# Sheet2.net
KiCad netlist of a schematic drawn in Altium Designer
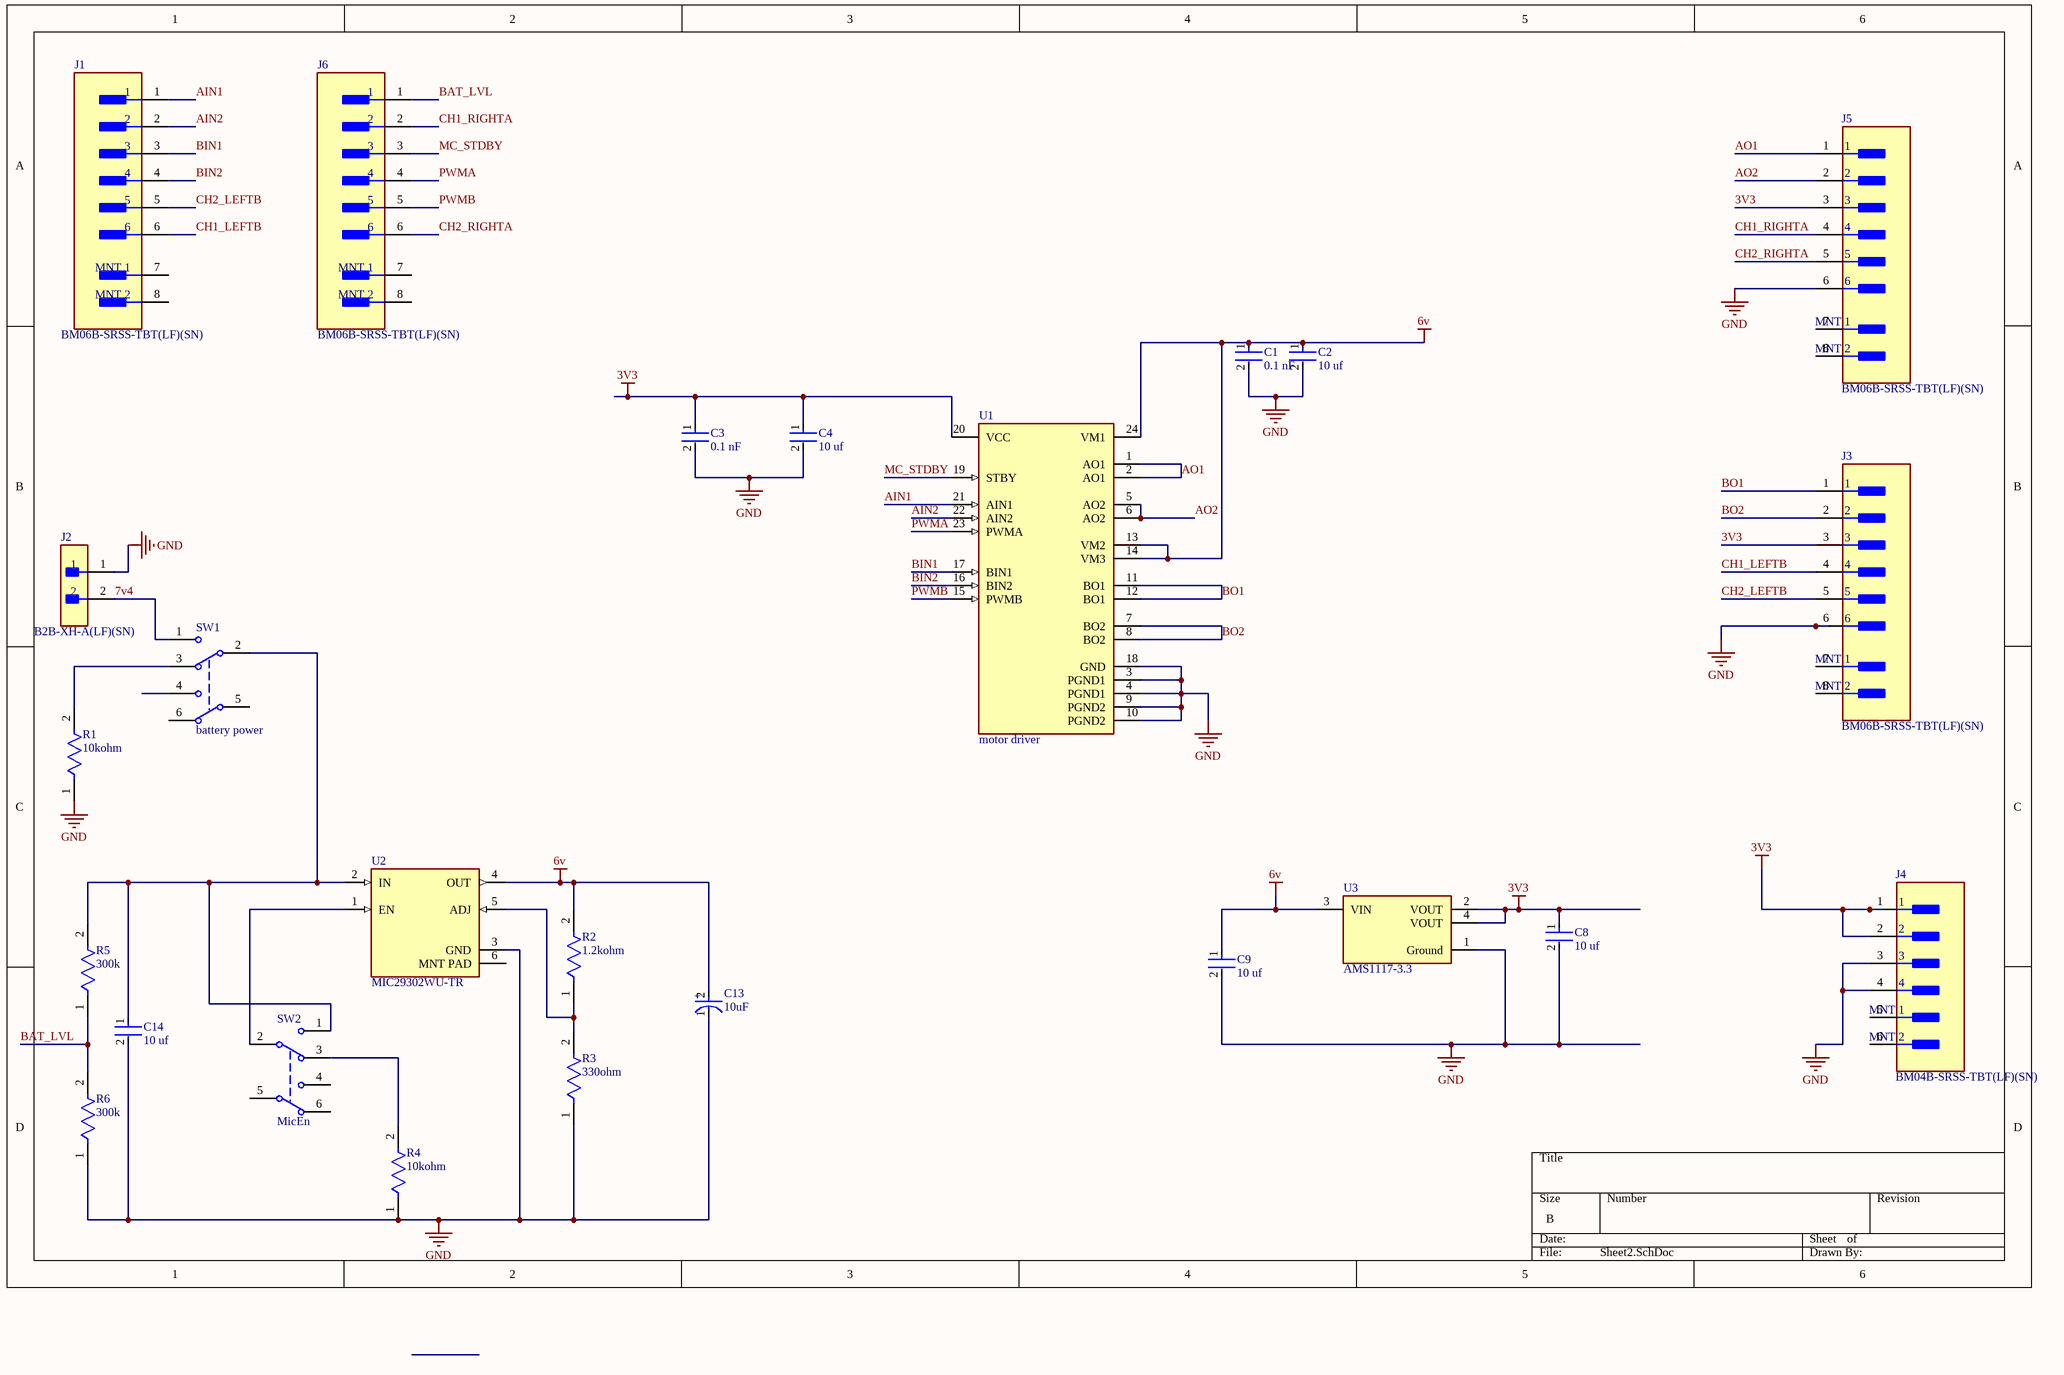
[diagram p0: Sheet2.SchDoc]

(export (version "E")
  (design (tool "Eeschema 10.0.6"))
  (components
    (comp (ref "C1")
      (value "0.1 nF")
      (footprint "FP-CC0805-0_85-MFG")
      (description "CAP CER 0.1UF 50V X7R 0805")
      (fields (field (name "TOLERANCE") "0.1") (field (name "MANUFACTURER PART NUMBER") "CC0805KRX7R9BB104"))
      (libsource (lib "Altium Content Vault") (part "11868f565c42a9108669ba33697ecf6"))
    )
    (comp (ref "C2")
      (value "10 uf")
      (footprint "FP-CC0805-0_2-1_45-IPC_A")
      (description "CAP CER 10UF 10V X5R 0805")
      (fields (field (name "VOLTAGE") "10V") (field (name "TOLERANCE") "10%"))
      (libsource (lib "Altium Content Vault") (part "e9c51b7dd13d4faca003ae77663ab08"))
    )
    (comp (ref "C3")
      (value "0.1 nF")
      (footprint "FP-CC0805-0_85-MFG")
      (description "CAP CER 0.1UF 50V X7R 0805")
      (fields (field (name "TOLERANCE") "0.1") (field (name "MANUFACTURER PART NUMBER") "CC0805KRX7R9BB104"))
      (libsource (lib "Altium Content Vault") (part "11868f565c42a9108669ba33697ecf6"))
    )
    (comp (ref "C4")
      (value "10 uf")
      (footprint "FP-CC0805-0_2-1_45-IPC_A")
      (description "CAP CER 10UF 10V X5R 0805")
      (fields (field (name "VOLTAGE") "10V") (field (name "TOLERANCE") "10%"))
      (libsource (lib "Altium Content Vault") (part "e9c51b7dd13d4faca003ae77663ab08"))
    )
    (comp (ref "C8")
      (value "10 uf")
      (footprint "FP-CC0805-0_2-1_45-IPC_A")
      (description "CAP CER 10UF 10V X5R 0805")
      (fields (field (name "VOLTAGE") "10V") (field (name "TOLERANCE") "10%"))
      (libsource (lib "Altium Content Vault") (part "e9c51b7dd13d4faca003ae77663ab08"))
    )
    (comp (ref "C9")
      (value "10 uf")
      (footprint "FP-CC0805-0_2-1_45-IPC_A")
      (description "CAP CER 10UF 10V X5R 0805")
      (fields (field (name "VOLTAGE") "10V") (field (name "TOLERANCE") "10%"))
      (libsource (lib "Altium Content Vault") (part "e9c51b7dd13d4faca003ae77663ab08"))
    )
    (comp (ref "C13")
      (value "10uF")
      (footprint "FP-T491A105K016AT-MFG")
      (description "CAP TANT 1UF 10% 16V 1206")
      (fields (field (name "TOLERANCE") "20%") (field (name "VOLTAGE") "16V"))
      (libsource (lib "Altium Content Vault") (part "203bc49f2ac43e59fd269a8c329ed05"))
    )
    (comp (ref "C14")
      (value "10 uf")
      (footprint "FP-CC0805-0_2-1_45-IPC_A")
      (description "CAP CER 10UF 10V X5R 0805")
      (fields (field (name "VOLTAGE") "10V") (field (name "TOLERANCE") "10%"))
      (libsource (lib "Altium Content Vault") (part "e9c51b7dd13d4faca003ae77663ab08"))
    )
    (comp (ref "J1")
      (value "BM06B-SRSS-TBT(LF)(SN)")
      (footprint "FP-BM06B-SRSS-TBT_LF_SN-MFG")
      (description "CONN HEADER SMD 6POS 1MM")
      (libsource (lib "") (part "ed24c53d9ba001d1a2a686240a95171_1"))
    )
    (comp (ref "J2")
      (value "B2B-XH-A(LF)(SN)")
      (footprint "FP-B2B-XH-A_LF_SN-MFG")
      (description "CONN HEADER VERT 2POS 2.5MM")
      (libsource (lib "Altium Content Vault") (part "3bc925449376181038e59eaffc5286c"))
    )
    (comp (ref "J3")
      (value "BM06B-SRSS-TBT(LF)(SN)")
      (footprint "FP-BM06B-SRSS-TBT_LF_SN-MFG")
      (description "CONN HEADER SMD 6POS 1MM")
      (libsource (lib "Altium Content Vault") (part "ed24c53d9ba001d1a2a686240a95171"))
    )
    (comp (ref "J4")
      (value "BM04B-SRSS-TBT(LF)(SN)")
      (footprint "FP-BM04B-SRSS-TBT_LF_SN-MFG")
      (description "CONN HEADER SMD 4POS 1MM")
      (libsource (lib "Altium Content Vault") (part "8e3688c4b118bffc0dd9b7401e414ba"))
    )
    (comp (ref "J5")
      (value "BM06B-SRSS-TBT(LF)(SN)")
      (footprint "FP-BM06B-SRSS-TBT_LF_SN-MFG")
      (description "CONN HEADER SMD 6POS 1MM")
      (libsource (lib "Altium Content Vault") (part "ed24c53d9ba001d1a2a686240a95171"))
    )
    (comp (ref "J6")
      (value "BM06B-SRSS-TBT(LF)(SN)")
      (footprint "FP-BM06B-SRSS-TBT_LF_SN-MFG")
      (description "CONN HEADER SMD 6POS 1MM")
      (libsource (lib "") (part "ed24c53d9ba001d1a2a686240a95171_1"))
    )
    (comp (ref "R1")
      (value "10kohm")
      (footprint "FP-CR0805-IPC_B")
      (description "Thick Film Chip Resistors 0805 10kΩ 0.125W 5% 200ppm/°C")
      (fields (field (name "TOLERANCE") "5%"))
      (libsource (lib "Altium Content Vault") (part "1029c3af85768c4190bb7ad29bc67b5"))
    )
    (comp (ref "R2")
      (value "1.2kohm")
      (footprint "FP-CR0805-IPC_B")
      (description "Thick Film Chip Resistors 0805 1kΩ 0.125W 1% 100ppm/°C")
      (fields (field (name "TOLERANCE") "1%"))
      (libsource (lib "Altium Content Vault") (part "1029c3af85768c4190bb7ad29bc67b5"))
    )
    (comp (ref "R3")
      (value "330ohm")
      (footprint "FP-CR0805-IPC_B")
      (description "Thick Film Chip Resistors 0805 330Ω 0.125W 1% 100ppm/°C")
      (fields (field (name "TOLERANCE") "1%"))
      (libsource (lib "Altium Content Vault") (part "1029c3af85768c4190bb7ad29bc67b5"))
    )
    (comp (ref "R4")
      (value "10kohm")
      (footprint "FP-CR0805-IPC_B")
      (description "Thick Film Chip Resistors 0805 10kΩ 0.125W 5% 200ppm/°C")
      (fields (field (name "TOLERANCE") "5%"))
      (libsource (lib "Altium Content Vault") (part "1029c3af85768c4190bb7ad29bc67b5"))
    )
    (comp (ref "R5")
      (value "300k")
      (footprint "FP-CR0805-IPC_B")
      (description "Thick Film Chip Resistors 0805 10kΩ 0.125W 5% 200ppm/°C")
      (fields (field (name "TOLERANCE") "5%"))
      (libsource (lib "Altium Content Vault") (part "1029c3af85768c4190bb7ad29bc67b5"))
    )
    (comp (ref "R6")
      (value "300k")
      (footprint "FP-CR0805-IPC_B")
      (description "Thick Film Chip Resistors 0805 10kΩ 0.125W 5% 200ppm/°C")
      (fields (field (name "TOLERANCE") "5%"))
      (libsource (lib "Altium Content Vault") (part "1029c3af85768c4190bb7ad29bc67b5"))
    )
    (comp (ref "SW1")
      (value "battery power")
      (footprint "452404020202")
      (description "452404020202 Slide Switch, Dpdt, 0.3A, 6Vdc, Tht Rohs Compliant: Yes")
      (libsource (lib "Altium Content Vault") (part "DPDT"))
    )
    (comp (ref "SW2")
      (value "MicEn")
      (footprint "452404020202")
      (description "452404020202 Slide Switch, Dpdt, 0.3A, 6Vdc, Tht Rohs Compliant: Yes")
      (libsource (lib "Altium Content Vault") (part "DPDT"))
    )
    (comp (ref "U1")
      (value "motor driver")
      (footprint "FP-SSOP24-P-300-0_65A-IPC_A")
      (description "IC MOTOR DRIVER 2.7V-5.5V 24SSOP")
      (libsource (lib "Altium Content Vault") (part "0e8a2fe7f3780dc9c50f4d41012bdec"))
    )
    (comp (ref "U2")
      (value "MIC29302WU-TR")
      (footprint "FP-C04-012-MFG")
      (description "IC REG LINEAR POS ADJ 3A TO263-5")
      (fields
        (field (name "MANUFACTURER") "Microchip")
        (field (name "OCTOPART") "https://octopart.com/mic29302wu-tr-microchip-66801318")
      )
      (libsource (lib "Altium Content Vault") (part "0db40f55fda0e91d0d14528974a446d"))
    )
    (comp (ref "U3")
      (value "AMS1117-3.3")
      (footprint "FP-AMS1117-IPC_C")
      (description "LDO Voltage Regulators 1A, 3.3V")
      (fields
        (field (name "OCTOPART") "https://octopart.com/ams1117-3.3-advanced+monolithic+systems-25899300")
        (field (name "MANUFACTURER") "Advanced Monolithic Systems")
      )
      (libsource (lib "Altium Content Vault") (part "8bdbb5f8e77002000e30dd2845d0354"))
    )
  )
  (nets
    (net (code "1") (name "/7v4") (class "Default")
      (node (ref "J2") (pin "2") (pinfunction "2_2") (pintype "passive"))
      (node (ref "SW1") (pin "1") (pinfunction "1_1") (pintype "passive"))
    )
    (net (code "2") (name "/AIN1") (class "Default")
      (node (ref "J1") (pin "1") (pinfunction "1_1") (pintype "passive"))
      (node (ref "U1") (pin "21") (pinfunction "AIN1_21") (pintype "input"))
    )
    (net (code "3") (name "/AIN2") (class "Default")
      (node (ref "J1") (pin "2") (pinfunction "2_2") (pintype "passive"))
      (node (ref "U1") (pin "22") (pinfunction "AIN2_22") (pintype "input"))
    )
    (net (code "4") (name "/AO1") (class "Default")
      (node (ref "J5") (pin "1") (pinfunction "1_1") (pintype "passive"))
      (node (ref "U1") (pin "1") (pinfunction "AO1_1") (pintype "passive"))
      (node (ref "U1") (pin "2") (pinfunction "AO1_2") (pintype "passive"))
    )
    (net (code "5") (name "/AO2") (class "Default")
      (node (ref "J5") (pin "2") (pinfunction "2_2") (pintype "passive"))
      (node (ref "U1") (pin "5") (pinfunction "AO2_5") (pintype "passive"))
      (node (ref "U1") (pin "6") (pinfunction "AO2_6") (pintype "passive"))
    )
    (net (code "6") (name "/BAT_LVL") (class "Default")
      (node (ref "J6") (pin "1") (pinfunction "1_1") (pintype "passive"))
      (node (ref "R5") (pin "1") (pinfunction "1_1") (pintype "passive"))
      (node (ref "R6") (pin "2") (pinfunction "2_2") (pintype "passive"))
    )
    (net (code "7") (name "/BIN1") (class "Default")
      (node (ref "J1") (pin "3") (pinfunction "3_3") (pintype "passive"))
      (node (ref "U1") (pin "17") (pinfunction "BIN1_17") (pintype "input"))
    )
    (net (code "8") (name "/BIN2") (class "Default")
      (node (ref "J1") (pin "4") (pinfunction "4_4") (pintype "passive"))
      (node (ref "U1") (pin "16") (pinfunction "BIN2_16") (pintype "input"))
    )
    (net (code "9") (name "/BO1") (class "Default")
      (node (ref "J3") (pin "1") (pinfunction "1_1") (pintype "passive"))
      (node (ref "U1") (pin "11") (pinfunction "BO1_11") (pintype "passive"))
      (node (ref "U1") (pin "12") (pinfunction "BO1_12") (pintype "passive"))
    )
    (net (code "10") (name "/BO2") (class "Default")
      (node (ref "J3") (pin "2") (pinfunction "2_2") (pintype "passive"))
      (node (ref "U1") (pin "7") (pinfunction "BO2_7") (pintype "passive"))
      (node (ref "U1") (pin "8") (pinfunction "BO2_8") (pintype "passive"))
    )
    (net (code "11") (name "/CH1_LEFTB") (class "Default")
      (node (ref "J1") (pin "6") (pinfunction "6_6") (pintype "passive"))
      (node (ref "J3") (pin "4") (pinfunction "4_4") (pintype "passive"))
    )
    (net (code "12") (name "/CH1_RIGHTA") (class "Default")
      (node (ref "J5") (pin "4") (pinfunction "4_4") (pintype "passive"))
      (node (ref "J6") (pin "2") (pinfunction "2_2") (pintype "passive"))
    )
    (net (code "13") (name "/CH2_LEFTB") (class "Default")
      (node (ref "J1") (pin "5") (pinfunction "5_5") (pintype "passive"))
      (node (ref "J3") (pin "5") (pinfunction "5_5") (pintype "passive"))
    )
    (net (code "14") (name "/CH2_RIGHTA") (class "Default")
      (node (ref "J5") (pin "5") (pinfunction "5_5") (pintype "passive"))
      (node (ref "J6") (pin "6") (pinfunction "6_6") (pintype "passive"))
    )
    (net (code "15") (name "/MC_STDBY") (class "Default")
      (node (ref "J6") (pin "3") (pinfunction "3_3") (pintype "passive"))
      (node (ref "U1") (pin "19") (pinfunction "STBY_19") (pintype "input"))
    )
    (net (code "16") (name "/PWMA") (class "Default")
      (node (ref "J6") (pin "4") (pinfunction "4_4") (pintype "passive"))
      (node (ref "U1") (pin "23") (pinfunction "PWMA_23") (pintype "input"))
    )
    (net (code "17") (name "/PWMB") (class "Default")
      (node (ref "J6") (pin "5") (pinfunction "5_5") (pintype "passive"))
      (node (ref "U1") (pin "15") (pinfunction "PWMB_15") (pintype "input"))
    )
    (net (code "18") (name "3V3") (class "Default")
      (node (ref "C3") (pin "1") (pinfunction "1_1") (pintype "passive"))
      (node (ref "C4") (pin "1") (pinfunction "1_1") (pintype "passive"))
      (node (ref "C8") (pin "1") (pinfunction "1_1") (pintype "passive"))
      (node (ref "J3") (pin "3") (pinfunction "3_3") (pintype "passive"))
      (node (ref "J4") (pin "1") (pinfunction "1_1") (pintype "passive"))
      (node (ref "J4") (pin "2") (pinfunction "2_2") (pintype "passive"))
      (node (ref "J5") (pin "3") (pinfunction "3_3") (pintype "passive"))
      (node (ref "U1") (pin "20") (pinfunction "VCC_20") (pintype "power_in"))
      (node (ref "U3") (pin "2") (pinfunction "VOUT_2") (pintype "passive"))
      (node (ref "U3") (pin "4") (pinfunction "VOUT_4") (pintype "passive"))
    )
    (net (code "19") (name "6v") (class "Default")
      (node (ref "C1") (pin "1") (pinfunction "1_1") (pintype "passive"))
      (node (ref "C13") (pin "2") (pinfunction "A_2") (pintype "passive"))
      (node (ref "C2") (pin "1") (pinfunction "1_1") (pintype "passive"))
      (node (ref "C9") (pin "1") (pinfunction "1_1") (pintype "passive"))
      (node (ref "R2") (pin "2") (pinfunction "2_2") (pintype "passive"))
      (node (ref "U1") (pin "13") (pinfunction "VM2_13") (pintype "passive"))
      (node (ref "U1") (pin "14") (pinfunction "VM3_14") (pintype "passive"))
      (node (ref "U1") (pin "24") (pinfunction "VM1_24") (pintype "passive"))
      (node (ref "U2") (pin "4") (pinfunction "OUT_4") (pintype "output"))
      (node (ref "U3") (pin "3") (pinfunction "VIN_3") (pintype "passive"))
    )
    (net (code "20") (name "GND") (class "Default")
      (node (ref "C1") (pin "2") (pinfunction "2_2") (pintype "passive"))
      (node (ref "C13") (pin "1") (pinfunction "C_1") (pintype "passive"))
      (node (ref "C14") (pin "2") (pinfunction "2_2") (pintype "passive"))
      (node (ref "C2") (pin "2") (pinfunction "2_2") (pintype "passive"))
      (node (ref "C3") (pin "2") (pinfunction "2_2") (pintype "passive"))
      (node (ref "C4") (pin "2") (pinfunction "2_2") (pintype "passive"))
      (node (ref "C8") (pin "2") (pinfunction "2_2") (pintype "passive"))
      (node (ref "C9") (pin "2") (pinfunction "2_2") (pintype "passive"))
      (node (ref "J2") (pin "1") (pinfunction "1_1") (pintype "passive"))
      (node (ref "J3") (pin "6") (pinfunction "6_6") (pintype "passive"))
      (node (ref "J4") (pin "3") (pinfunction "3_3") (pintype "passive"))
      (node (ref "J4") (pin "4") (pinfunction "4_4") (pintype "passive"))
      (node (ref "J5") (pin "6") (pinfunction "6_6") (pintype "passive"))
      (node (ref "R1") (pin "1") (pinfunction "1_1") (pintype "passive"))
      (node (ref "R3") (pin "1") (pinfunction "1_1") (pintype "passive"))
      (node (ref "R4") (pin "1") (pinfunction "1_1") (pintype "passive"))
      (node (ref "R6") (pin "1") (pinfunction "1_1") (pintype "passive"))
      (node (ref "U1") (pin "10") (pinfunction "PGND2_10") (pintype "power_in"))
      (node (ref "U1") (pin "18") (pinfunction "GND_18") (pintype "power_in"))
      (node (ref "U1") (pin "3") (pinfunction "PGND1_3") (pintype "power_in"))
      (node (ref "U1") (pin "4") (pinfunction "PGND1_4") (pintype "power_in"))
      (node (ref "U1") (pin "9") (pinfunction "PGND2_9") (pintype "power_in"))
      (node (ref "U2") (pin "3") (pinfunction "GND_3") (pintype "power_in"))
      (node (ref "U3") (pin "1") (pinfunction "Ground_1") (pintype "power_in"))
    )
    (net (code "21") (name "Net-(R1-Pad2)") (class "Default")
      (node (ref "R1") (pin "2") (pinfunction "2_2") (pintype "passive"))
      (node (ref "SW1") (pin "3") (pinfunction "3_3") (pintype "passive"))
    )
    (net (code "22") (name "Net-(R4-Pad2)") (class "Default")
      (node (ref "R4") (pin "2") (pinfunction "2_2") (pintype "passive"))
      (node (ref "SW2") (pin "3") (pinfunction "3_3") (pintype "passive"))
    )
    (net (code "23") (name "Net-(U2-ADJ)") (class "Default")
      (node (ref "R2") (pin "1") (pinfunction "1_1") (pintype "passive"))
      (node (ref "R3") (pin "2") (pinfunction "2_2") (pintype "passive"))
      (node (ref "U2") (pin "5") (pinfunction "ADJ_5") (pintype "input"))
    )
    (net (code "24") (name "Net-(U2-EN)") (class "Default")
      (node (ref "SW2") (pin "2") (pinfunction "2_2") (pintype "passive"))
      (node (ref "U2") (pin "1") (pinfunction "EN_1") (pintype "input"))
    )
    (net (code "25") (name "Net-(U2-IN)") (class "Default")
      (node (ref "C14") (pin "1") (pinfunction "1_1") (pintype "passive"))
      (node (ref "R5") (pin "2") (pinfunction "2_2") (pintype "passive"))
      (node (ref "SW1") (pin "2") (pinfunction "2_2") (pintype "passive"))
      (node (ref "SW2") (pin "1") (pinfunction "1_1") (pintype "passive"))
      (node (ref "U2") (pin "2") (pinfunction "IN_2") (pintype "input"))
    )
    (net (code "26") (name "unconnected-(J1-MNT_1-Pad7)") (class "Default")
      (node (ref "J1") (pin "7") (pinfunction "MNT_1_7") (pintype "passive"))
    )
    (net (code "27") (name "unconnected-(J1-MNT_2-Pad8)") (class "Default")
      (node (ref "J1") (pin "8") (pinfunction "MNT_2_8") (pintype "passive"))
    )
    (net (code "28") (name "unconnected-(J3-MNT_1-Pad7)") (class "Default")
      (node (ref "J3") (pin "7") (pinfunction "MNT_1_7") (pintype "passive"))
    )
    (net (code "29") (name "unconnected-(J3-MNT_2-Pad8)") (class "Default")
      (node (ref "J3") (pin "8") (pinfunction "MNT_2_8") (pintype "passive"))
    )
    (net (code "30") (name "unconnected-(J4-MNT_1-Pad5)") (class "Default")
      (node (ref "J4") (pin "5") (pinfunction "MNT_1_5") (pintype "passive"))
    )
    (net (code "31") (name "unconnected-(J4-MNT_2-Pad6)") (class "Default")
      (node (ref "J4") (pin "6") (pinfunction "MNT_2_6") (pintype "passive"))
    )
    (net (code "32") (name "unconnected-(J5-MNT_1-Pad7)") (class "Default")
      (node (ref "J5") (pin "7") (pinfunction "MNT_1_7") (pintype "passive"))
    )
    (net (code "33") (name "unconnected-(J5-MNT_2-Pad8)") (class "Default")
      (node (ref "J5") (pin "8") (pinfunction "MNT_2_8") (pintype "passive"))
    )
    (net (code "34") (name "unconnected-(J6-MNT_1-Pad7)") (class "Default")
      (node (ref "J6") (pin "7") (pinfunction "MNT_1_7") (pintype "passive"))
    )
    (net (code "35") (name "unconnected-(J6-MNT_2-Pad8)") (class "Default")
      (node (ref "J6") (pin "8") (pinfunction "MNT_2_8") (pintype "passive"))
    )
    (net (code "36") (name "unconnected-(SW1-Pad4)") (class "Default")
      (node (ref "SW1") (pin "4") (pinfunction "4_4") (pintype "passive"))
    )
    (net (code "37") (name "unconnected-(SW1-Pad5)") (class "Default")
      (node (ref "SW1") (pin "5") (pinfunction "5_5") (pintype "passive"))
    )
    (net (code "38") (name "unconnected-(SW1-Pad6)") (class "Default")
      (node (ref "SW1") (pin "6") (pinfunction "6_6") (pintype "passive"))
    )
    (net (code "39") (name "unconnected-(SW2-Pad4)") (class "Default")
      (node (ref "SW2") (pin "4") (pinfunction "4_4") (pintype "passive"))
    )
    (net (code "40") (name "unconnected-(SW2-Pad5)") (class "Default")
      (node (ref "SW2") (pin "5") (pinfunction "5_5") (pintype "passive"))
    )
    (net (code "41") (name "unconnected-(SW2-Pad6)") (class "Default")
      (node (ref "SW2") (pin "6") (pinfunction "6_6") (pintype "passive"))
    )
    (net (code "42") (name "unconnected-(U2-MNT_PAD-Pad6)") (class "Default")
      (node (ref "U2") (pin "6") (pinfunction "MNT_PAD_6") (pintype "passive"))
    )
  )
)
